# perica3.net
KiCad netlist of a schematic drawn in EAGLE
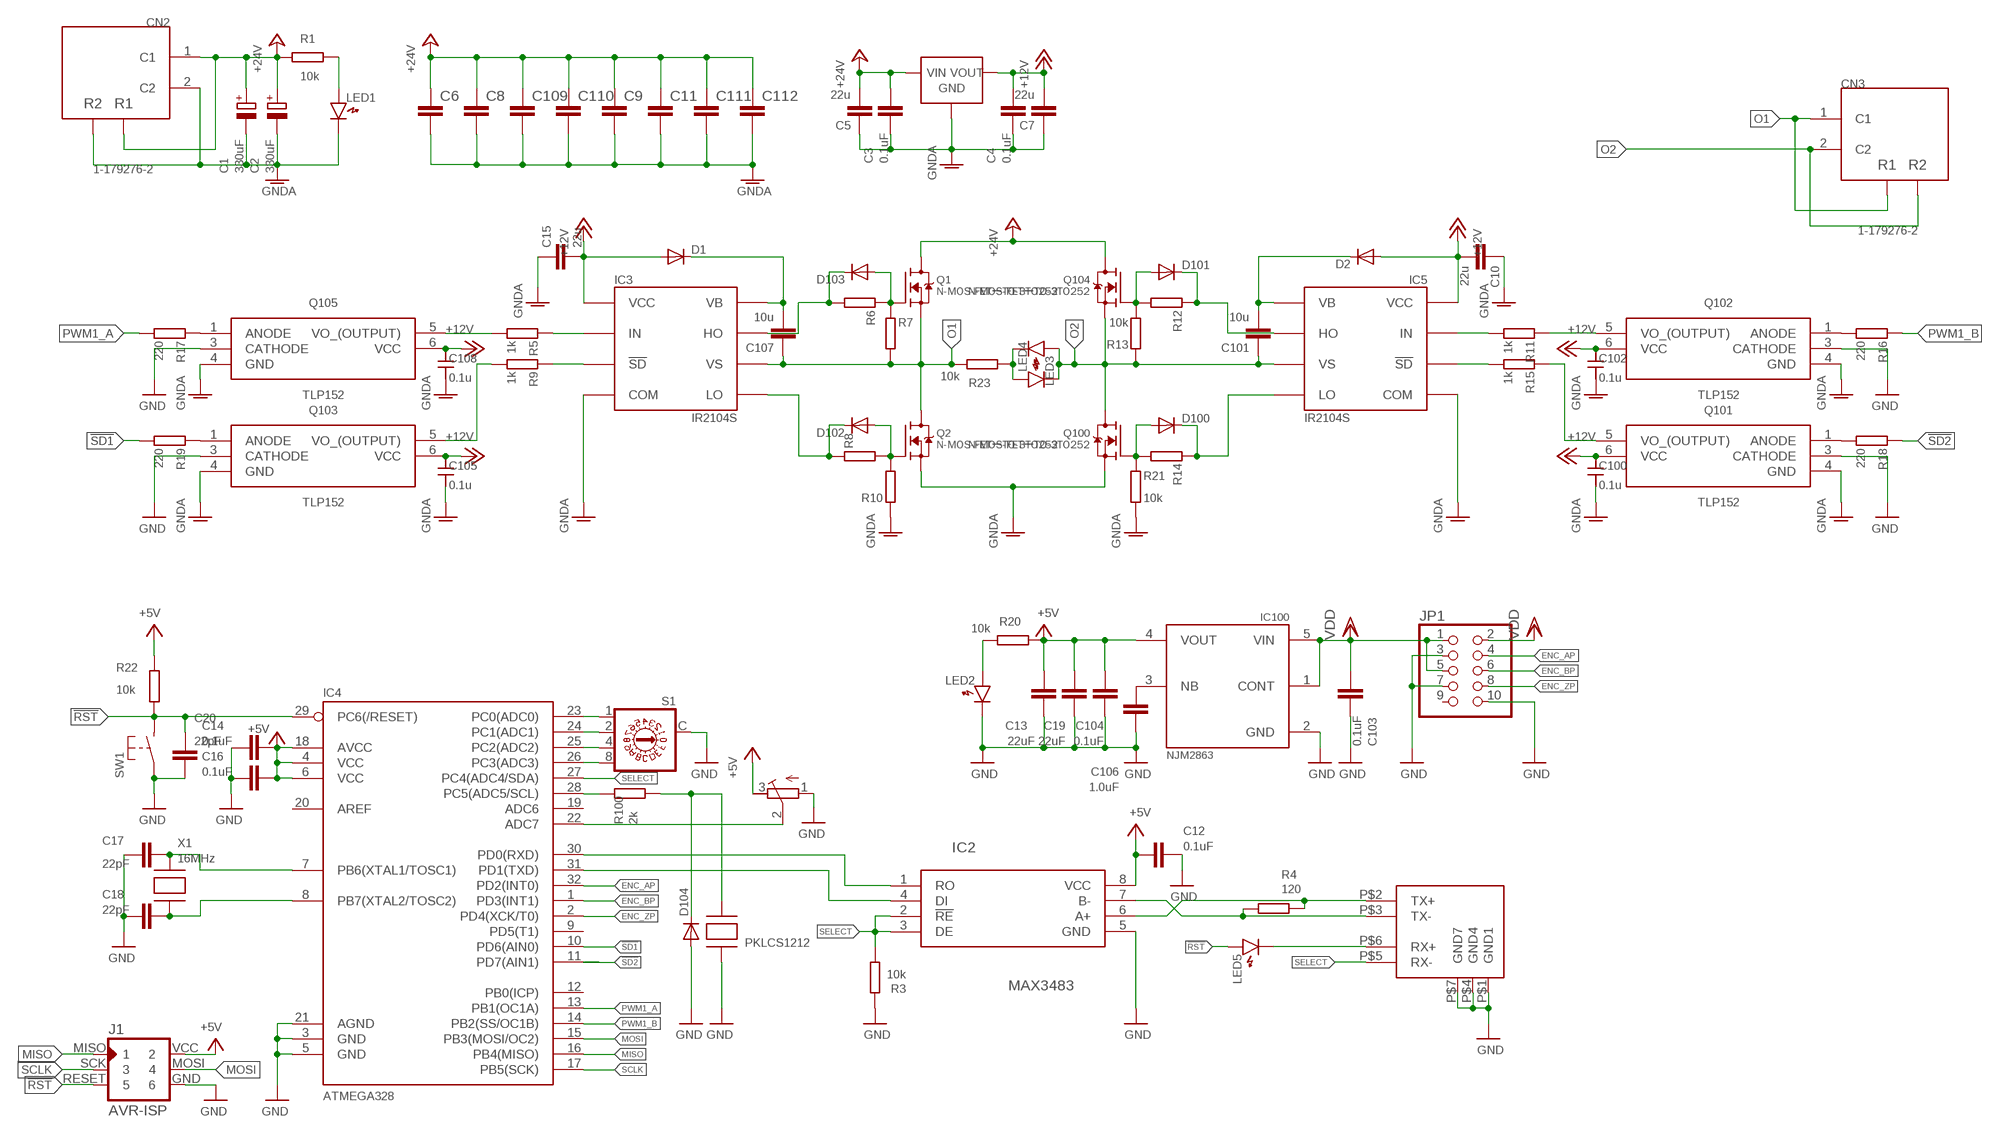
[diagram p0: schematic, sheet 1]

(export (version "E")
  (design (tool "Eeschema 10.0.6"))
  (components
    (comp (ref "C1")
      (value "330uF")
      (footprint "eagle-import:UD-10X10_NICHICON")
      (libsource (lib "eagle-import") (part "CPOL-EUUD-10X10"))
    )
    (comp (ref "C2")
      (value "330uF")
      (footprint "eagle-import:UD-10X10_NICHICON")
      (libsource (lib "eagle-import") (part "CPOL-EUUD-10X10"))
    )
    (comp (ref "C3")
      (value "0.1uF")
      (footprint "eagle-import:C0603K")
      (libsource (lib "eagle-import") (part "resistor_C-EUC0603K"))
    )
    (comp (ref "C4")
      (value "0.1uF")
      (footprint "eagle-import:C0603K")
      (libsource (lib "eagle-import") (part "resistor_C-EUC0603K"))
    )
    (comp (ref "C5")
      (value "22u")
      (footprint "eagle-import:C1206K")
      (libsource (lib "eagle-import") (part "C-EUC1206K"))
    )
    (comp (ref "C6")
      (value "C-EUC1206")
      (footprint "eagle-import:C1206")
      (libsource (lib "eagle-import") (part "C-EUC1206"))
    )
    (comp (ref "C7")
      (value "22u")
      (footprint "eagle-import:C1206K")
      (libsource (lib "eagle-import") (part "C-EUC1206K"))
    )
    (comp (ref "C8")
      (value "C-EUC1206")
      (footprint "eagle-import:C1206")
      (libsource (lib "eagle-import") (part "C-EUC1206"))
    )
    (comp (ref "C9")
      (value "C-EUC1206")
      (footprint "eagle-import:C1206")
      (libsource (lib "eagle-import") (part "C-EUC1206"))
    )
    (comp (ref "C10")
      (value "22u")
      (footprint "eagle-import:C1206K")
      (libsource (lib "eagle-import") (part "C-EUC1206K"))
    )
    (comp (ref "C11")
      (value "C-EUC1206")
      (footprint "eagle-import:C1206")
      (libsource (lib "eagle-import") (part "C-EUC1206"))
    )
    (comp (ref "C12")
      (value "0.1uF")
      (footprint "eagle-import:C0603K")
      (libsource (lib "eagle-import") (part "resistor_C-EUC0603K"))
    )
    (comp (ref "C13")
      (value "22uF")
      (footprint "eagle-import:C0805K")
      (libsource (lib "eagle-import") (part "resistor_C-EUC0805K"))
    )
    (comp (ref "C14")
      (value "0.1uF")
      (footprint "eagle-import:C0603K")
      (libsource (lib "eagle-import") (part "resistor_C-EUC0603K"))
    )
    (comp (ref "C15")
      (value "22u")
      (footprint "eagle-import:C1206K")
      (libsource (lib "eagle-import") (part "C-EUC1206K"))
    )
    (comp (ref "C16")
      (value "0.1uF")
      (footprint "eagle-import:C0603K")
      (libsource (lib "eagle-import") (part "resistor_C-EUC0603K"))
    )
    (comp (ref "C17")
      (value "22pF")
      (footprint "eagle-import:C0603K")
      (libsource (lib "eagle-import") (part "resistor_C-EUC0603K"))
    )
    (comp (ref "C18")
      (value "22pF")
      (footprint "eagle-import:C0603K")
      (libsource (lib "eagle-import") (part "resistor_C-EUC0603K"))
    )
    (comp (ref "C19")
      (value "22uF")
      (footprint "eagle-import:C0805K")
      (libsource (lib "eagle-import") (part "resistor_C-EUC0805K"))
    )
    (comp (ref "C20")
      (value "22pF")
      (footprint "eagle-import:C0603K")
      (libsource (lib "eagle-import") (part "resistor_C-EUC0603K"))
    )
    (comp (ref "C100")
      (value "0.1u")
      (footprint "eagle-import:SMD1608")
      (libsource (lib "eagle-import") (part "CAPACTOR1608"))
    )
    (comp (ref "C101")
      (value "10u")
      (footprint "eagle-import:C1206K")
      (libsource (lib "eagle-import") (part "C-EUC1206K"))
    )
    (comp (ref "C102")
      (value "0.1u")
      (footprint "eagle-import:SMD1608")
      (libsource (lib "eagle-import") (part "CAPACTOR1608"))
    )
    (comp (ref "C103")
      (value "0.1uF")
      (footprint "eagle-import:C0603K")
      (libsource (lib "eagle-import") (part "resistor_C-EUC0603K"))
    )
    (comp (ref "C104")
      (value "0.1uF")
      (footprint "eagle-import:C0603K")
      (libsource (lib "eagle-import") (part "resistor_C-EUC0603K"))
    )
    (comp (ref "C105")
      (value "0.1u")
      (footprint "eagle-import:SMD1608")
      (libsource (lib "eagle-import") (part "CAPACTOR1608"))
    )
    (comp (ref "C106")
      (value "1.0uF")
      (footprint "eagle-import:C0603K")
      (libsource (lib "eagle-import") (part "resistor_C-EUC0603K"))
    )
    (comp (ref "C107")
      (value "10u")
      (footprint "eagle-import:C1206K")
      (libsource (lib "eagle-import") (part "C-EUC1206K"))
    )
    (comp (ref "C108")
      (value "0.1u")
      (footprint "eagle-import:SMD1608")
      (libsource (lib "eagle-import") (part "CAPACTOR1608"))
    )
    (comp (ref "C109")
      (value "C-EUC1206")
      (footprint "eagle-import:C1206")
      (libsource (lib "eagle-import") (part "C-EUC1206"))
    )
    (comp (ref "C110")
      (value "C-EUC1206")
      (footprint "eagle-import:C1206")
      (libsource (lib "eagle-import") (part "C-EUC1206"))
    )
    (comp (ref "C111")
      (value "C-EUC1206")
      (footprint "eagle-import:C1206")
      (libsource (lib "eagle-import") (part "C-EUC1206"))
    )
    (comp (ref "C112")
      (value "C-EUC1206")
      (footprint "eagle-import:C1206")
      (libsource (lib "eagle-import") (part "C-EUC1206"))
    )
    (comp (ref "CN1")
      (value "SATA")
      (footprint "eagle-import:SATA_MOLEX_LLC_0470804001")
      (libsource (lib "eagle-import") (part "SATA"))
    )
    (comp (ref "CN2")
      (value "1-179276-2")
      (footprint "eagle-import:1-179276-2")
      (fields (field (name "MANUFACTURER_PART_NUMBER") "11792762"))
      (libsource (lib "eagle-import") (part "1-179276-2"))
    )
    (comp (ref "CN3")
      (value "1-179276-2")
      (footprint "eagle-import:1-179276-2")
      (fields (field (name "MANUFACTURER_PART_NUMBER") "11792762"))
      (libsource (lib "eagle-import") (part "1-179276-2"))
    )
    (comp (ref "D1")
      (value "DIODE-SOD123")
      (footprint "eagle-import:SOD123")
      (libsource (lib "eagle-import") (part "DIODE-SOD123"))
    )
    (comp (ref "D2")
      (value "DIODE-SOD123")
      (footprint "eagle-import:SOD123")
      (libsource (lib "eagle-import") (part "DIODE-SOD123"))
    )
    (comp (ref "D100")
      (value "DIODE-SOD123")
      (footprint "eagle-import:SOD123")
      (libsource (lib "eagle-import") (part "DIODE-SOD123"))
    )
    (comp (ref "D101")
      (value "DIODE-SOD123")
      (footprint "eagle-import:SOD123")
      (libsource (lib "eagle-import") (part "DIODE-SOD123"))
    )
    (comp (ref "D102")
      (value "DIODE-SOD123")
      (footprint "eagle-import:SOD123")
      (libsource (lib "eagle-import") (part "DIODE-SOD123"))
    )
    (comp (ref "D103")
      (value "DIODE-SOD123")
      (footprint "eagle-import:SOD123")
      (libsource (lib "eagle-import") (part "DIODE-SOD123"))
    )
    (comp (ref "D104")
      (value "DIODE-SOD123")
      (footprint "eagle-import:SOD123")
      (libsource (lib "eagle-import") (part "DIODE-SOD123"))
    )
    (comp (ref "IC1")
      (value "NJM78XX")
      (footprint "eagle-import:TO252")
      (libsource (lib "eagle-import") (part "NJM78XX"))
    )
    (comp (ref "IC2")
      (value "MAX3483")
      (footprint "eagle-import:SO-8")
      (libsource (lib "eagle-import") (part "MAX3488"))
    )
    (comp (ref "IC3")
      (value "IR2104S")
      (footprint "eagle-import:SO-8")
      (libsource (lib "eagle-import") (part "IR2104S"))
    )
    (comp (ref "IC4")
      (value "ATMEGA328")
      (footprint "eagle-import:TQFP32-08")
      (libsource (lib "eagle-import") (part "ATMEGA328"))
    )
    (comp (ref "IC5")
      (value "IR2104S")
      (footprint "eagle-import:SO-8")
      (libsource (lib "eagle-import") (part "IR2104S"))
    )
    (comp (ref "IC100")
      (value "NJM2863")
      (footprint "eagle-import:SOT-23-5")
      (libsource (lib "eagle-import") (part "NJM2863"))
    )
    (comp (ref "J1")
      (value "AVR-ISP")
      (footprint "eagle-import:AVR-ISP-6PIN-SMAILL-SILK")
      (libsource (lib "eagle-import") (part "AVR-ISP-6PINAVR-ISP-6PIN-SMALL-SILK"))
    )
    (comp (ref "JP1")
      (value "PINHD-2X5")
      (footprint "eagle-import:2X05")
      (libsource (lib "eagle-import") (part "PINHD-2X5"))
    )
    (comp (ref "LED1")
      (value "RED")
      (footprint "eagle-import:LED_1608")
      (libsource (lib "eagle-import") (part "LED"))
    )
    (comp (ref "LED2")
      (value "RED")
      (footprint "eagle-import:LED_1608")
      (libsource (lib "eagle-import") (part "LED"))
    )
    (comp (ref "LED3")
      (value "RED")
      (footprint "eagle-import:LED_1608")
      (libsource (lib "eagle-import") (part "LED"))
    )
    (comp (ref "LED4")
      (value "RED")
      (footprint "eagle-import:LED_1608")
      (libsource (lib "eagle-import") (part "LED"))
    )
    (comp (ref "LED5")
      (value "RED")
      (footprint "eagle-import:LED_1608")
      (libsource (lib "eagle-import") (part "LED"))
    )
    (comp (ref "Q1")
      (value "N-MOS-FETーTO-3TO252")
      (footprint "eagle-import:TO252")
      (libsource (lib "eagle-import") (part "N-MOS-FETーTO-3TO252"))
    )
    (comp (ref "Q2")
      (value "N-MOS-FETーTO-3TO252")
      (footprint "eagle-import:TO252")
      (libsource (lib "eagle-import") (part "N-MOS-FETーTO-3TO252"))
    )
    (comp (ref "Q100")
      (value "N-MOS-FETーTO-3TO252")
      (footprint "eagle-import:TO252")
      (libsource (lib "eagle-import") (part "N-MOS-FETーTO-3TO252"))
    )
    (comp (ref "Q101")
      (value "TLP152")
      (footprint "eagle-import:11-4L1S(5-PIN-SOIC)")
      (fields (field (name "MANUFACTURER_PART_NUMBER") "TLP2309") (field (name "RS_PART_NUMBER") "7965241P"))
      (libsource (lib "eagle-import") (part "TLP2309"))
    )
    (comp (ref "Q102")
      (value "TLP152")
      (footprint "eagle-import:11-4L1S(5-PIN-SOIC)")
      (fields (field (name "MANUFACTURER_PART_NUMBER") "TLP2309") (field (name "RS_PART_NUMBER") "7965241P"))
      (libsource (lib "eagle-import") (part "TLP2309"))
    )
    (comp (ref "Q103")
      (value "TLP152")
      (footprint "eagle-import:11-4L1S(5-PIN-SOIC)")
      (fields (field (name "MANUFACTURER_PART_NUMBER") "TLP2309") (field (name "RS_PART_NUMBER") "7965241P"))
      (libsource (lib "eagle-import") (part "TLP2309"))
    )
    (comp (ref "Q104")
      (value "N-MOS-FETーTO-3TO252")
      (footprint "eagle-import:TO252")
      (libsource (lib "eagle-import") (part "N-MOS-FETーTO-3TO252"))
    )
    (comp (ref "Q105")
      (value "TLP152")
      (footprint "eagle-import:11-4L1S(5-PIN-SOIC)")
      (fields (field (name "MANUFACTURER_PART_NUMBER") "TLP2309") (field (name "RS_PART_NUMBER") "7965241P"))
      (libsource (lib "eagle-import") (part "TLP2309"))
    )
    (comp (ref "R1")
      (value "10k")
      (footprint "eagle-import:SMD1608")
      (libsource (lib "eagle-import") (part "REGISTER1068"))
    )
    (comp (ref "R2")
      (value "10k-20k")
      (footprint "eagle-import:RTRIM4G_J")
      (libsource (lib "eagle-import") (part "R-TRIMM4G/J"))
    )
    (comp (ref "R3")
      (value "10k")
      (footprint "eagle-import:SMD1608")
      (libsource (lib "eagle-import") (part "REGISTER1068"))
    )
    (comp (ref "R4")
      (value "120")
      (footprint "eagle-import:SMD1608")
      (libsource (lib "eagle-import") (part "REGISTER1068"))
    )
    (comp (ref "R5")
      (value "1k")
      (footprint "eagle-import:SMD1608")
      (libsource (lib "eagle-import") (part "REGISTER1068"))
    )
    (comp (ref "R6")
      (value "REGISTER1068")
      (footprint "eagle-import:SMD1608")
      (libsource (lib "eagle-import") (part "REGISTER1068"))
    )
    (comp (ref "R7")
      (value "REGISTER1068")
      (footprint "eagle-import:SMD1608")
      (libsource (lib "eagle-import") (part "REGISTER1068"))
    )
    (comp (ref "R8")
      (value "REGISTER1068")
      (footprint "eagle-import:SMD1608")
      (libsource (lib "eagle-import") (part "REGISTER1068"))
    )
    (comp (ref "R9")
      (value "1k")
      (footprint "eagle-import:SMD1608")
      (libsource (lib "eagle-import") (part "REGISTER1068"))
    )
    (comp (ref "R10")
      (value "REGISTER1068")
      (footprint "eagle-import:SMD1608")
      (libsource (lib "eagle-import") (part "REGISTER1068"))
    )
    (comp (ref "R11")
      (value "1k")
      (footprint "eagle-import:SMD1608")
      (libsource (lib "eagle-import") (part "REGISTER1068"))
    )
    (comp (ref "R12")
      (value "REGISTER1068")
      (footprint "eagle-import:SMD1608")
      (libsource (lib "eagle-import") (part "REGISTER1068"))
    )
    (comp (ref "R13")
      (value "10k")
      (footprint "eagle-import:SMD1608")
      (libsource (lib "eagle-import") (part "REGISTER1068"))
    )
    (comp (ref "R14")
      (value "REGISTER1068")
      (footprint "eagle-import:SMD1608")
      (libsource (lib "eagle-import") (part "REGISTER1068"))
    )
    (comp (ref "R15")
      (value "1k")
      (footprint "eagle-import:SMD1608")
      (libsource (lib "eagle-import") (part "REGISTER1068"))
    )
    (comp (ref "R16")
      (value "220")
      (footprint "eagle-import:SMD1608")
      (libsource (lib "eagle-import") (part "REGISTER1068"))
    )
    (comp (ref "R17")
      (value "220")
      (footprint "eagle-import:SMD1608")
      (libsource (lib "eagle-import") (part "REGISTER1068"))
    )
    (comp (ref "R18")
      (value "220")
      (footprint "eagle-import:SMD1608")
      (libsource (lib "eagle-import") (part "REGISTER1068"))
    )
    (comp (ref "R19")
      (value "220")
      (footprint "eagle-import:SMD1608")
      (libsource (lib "eagle-import") (part "REGISTER1068"))
    )
    (comp (ref "R20")
      (value "10k")
      (footprint "eagle-import:SMD1608")
      (libsource (lib "eagle-import") (part "REGISTER1068"))
    )
    (comp (ref "R21")
      (value "10k")
      (footprint "eagle-import:SMD1608")
      (libsource (lib "eagle-import") (part "REGISTER1068"))
    )
    (comp (ref "R22")
      (value "10k")
      (footprint "eagle-import:SMD1608")
      (libsource (lib "eagle-import") (part "REGISTER1068"))
    )
    (comp (ref "R23")
      (value "10k")
      (footprint "eagle-import:SMD1608")
      (libsource (lib "eagle-import") (part "REGISTER1068"))
    )
    (comp (ref "R100")
      (value "2k")
      (footprint "eagle-import:SMD1608")
      (libsource (lib "eagle-import") (part "REGISTER1068"))
    )
    (comp (ref "S1")
      (value "P103")
      (footprint "eagle-import:P103")
      (libsource (lib "eagle-import") (part "P103"))
    )
    (comp (ref "SW1")
      (value "TUCT_SW_MINI")
      (footprint "eagle-import:SW1")
      (libsource (lib "eagle-import") (part "TUCT_SW_MINI"))
    )
    (comp (ref "X1")
      (value "16MHz")
      (footprint "eagle-import:NX5032")
      (libsource (lib "eagle-import") (part "XTALNX5032"))
    )
    (comp (ref "Z1")
      (value "PKLCS1212")
      (footprint "eagle-import:PKLCS1212")
      (libsource (lib "eagle-import") (part "PKLCS1212"))
    )
  )
  (nets
    (net (code "1") (name "+5V") (class "Default")
      (node (ref "C104") (pin "2") (pinfunction "2_2") (pintype "passive"))
      (node (ref "C12") (pin "2") (pinfunction "2_2") (pintype "passive"))
      (node (ref "C13") (pin "1") (pinfunction "1_1") (pintype "passive"))
      (node (ref "C14") (pin "2") (pinfunction "2_2") (pintype "passive"))
      (node (ref "C16") (pin "2") (pinfunction "2_2") (pintype "passive"))
      (node (ref "C19") (pin "1") (pinfunction "1_1") (pintype "passive"))
      (node (ref "IC100") (pin "4") (pinfunction "VOUT_4") (pintype "bidirectional"))
      (node (ref "IC2") (pin "8") (pinfunction "VCC_8") (pintype "power_in"))
      (node (ref "IC4") (pin "18") (pinfunction "AVCC_18") (pintype "bidirectional"))
      (node (ref "IC4") (pin "4") (pinfunction "VCC_4") (pintype "bidirectional"))
      (node (ref "IC4") (pin "6") (pinfunction "VCC_6") (pintype "bidirectional"))
      (node (ref "J1") (pin "VCC") (pinfunction "2_VCC") (pintype "passive"))
      (node (ref "R2") (pin "3") (pinfunction "E_3") (pintype "passive"))
      (node (ref "R20") (pin "2") (pinfunction "2_2") (pintype "passive"))
      (node (ref "R22") (pin "2") (pinfunction "2_2") (pintype "passive"))
    )
    (net (code "2") (name "+12V") (class "Default")
      (node (ref "C10") (pin "2") (pinfunction "2_2") (pintype "passive"))
      (node (ref "C100") (pin "1") (pinfunction "1_1") (pintype "passive"))
      (node (ref "C102") (pin "1") (pinfunction "1_1") (pintype "passive"))
      (node (ref "C105") (pin "1") (pinfunction "1_1") (pintype "passive"))
      (node (ref "C108") (pin "1") (pinfunction "1_1") (pintype "passive"))
      (node (ref "C15") (pin "2") (pinfunction "2_2") (pintype "passive"))
      (node (ref "C4") (pin "2") (pinfunction "2_2") (pintype "passive"))
      (node (ref "C7") (pin "2") (pinfunction "2_2") (pintype "passive"))
      (node (ref "D1") (pin "A") (pinfunction "A_A") (pintype "passive"))
      (node (ref "D2") (pin "A") (pinfunction "A_A") (pintype "passive"))
      (node (ref "IC1") (pin "2") (pinfunction "VOUT_2") (pintype "bidirectional"))
      (node (ref "IC3") (pin "1") (pinfunction "VCC_1") (pintype "bidirectional"))
      (node (ref "IC5") (pin "1") (pinfunction "VCC_1") (pintype "bidirectional"))
      (node (ref "Q101") (pin "6") (pinfunction "VCC_6") (pintype "input"))
      (node (ref "Q102") (pin "6") (pinfunction "VCC_6") (pintype "input"))
      (node (ref "Q103") (pin "6") (pinfunction "VCC_6") (pintype "input"))
      (node (ref "Q105") (pin "6") (pinfunction "VCC_6") (pintype "input"))
    )
    (net (code "3") (name "+24V") (class "Default")
      (node (ref "C1") (pin "+") (pinfunction "+_+") (pintype "passive"))
      (node (ref "C109") (pin "1") (pinfunction "1_1") (pintype "passive"))
      (node (ref "C11") (pin "1") (pinfunction "1_1") (pintype "passive"))
      (node (ref "C110") (pin "1") (pinfunction "1_1") (pintype "passive"))
      (node (ref "C111") (pin "1") (pinfunction "1_1") (pintype "passive"))
      (node (ref "C112") (pin "1") (pinfunction "1_1") (pintype "passive"))
      (node (ref "C2") (pin "+") (pinfunction "+_+") (pintype "passive"))
      (node (ref "C3") (pin "2") (pinfunction "2_2") (pintype "passive"))
      (node (ref "C5") (pin "2") (pinfunction "2_2") (pintype "passive"))
      (node (ref "C6") (pin "1") (pinfunction "1_1") (pintype "passive"))
      (node (ref "C8") (pin "1") (pinfunction "1_1") (pintype "passive"))
      (node (ref "C9") (pin "1") (pinfunction "1_1") (pintype "passive"))
      (node (ref "CN2") (pin "1") (pinfunction "C1_1") (pintype "passive"))
      (node (ref "CN2") (pin "4") (pinfunction "R1_4") (pintype "passive"))
      (node (ref "IC1") (pin "1") (pinfunction "VIN_1") (pintype "bidirectional"))
      (node (ref "Q1") (pin "3") (pinfunction "D_3") (pintype "bidirectional"))
      (node (ref "Q104") (pin "3") (pinfunction "D_3") (pintype "bidirectional"))
      (node (ref "R1") (pin "2") (pinfunction "2_2") (pintype "passive"))
    )
    (net (code "4") (name "/~{RST}") (class "Default")
      (node (ref "C20") (pin "2") (pinfunction "2_2") (pintype "passive"))
      (node (ref "IC4") (pin "29") (pinfunction "PC6(/RESET)_29") (pintype "bidirectional"))
      (node (ref "J1") (pin "RESET") (pinfunction "5_RESET") (pintype "passive"))
      (node (ref "LED5") (pin "A") (pinfunction "A_A") (pintype "passive"))
      (node (ref "R22") (pin "1") (pinfunction "1_1") (pintype "passive"))
      (node (ref "SW1") (pin "P$2") (pinfunction "S_P$2") (pintype "passive"))
    )
    (net (code "5") (name "/~{SD1}") (class "Default")
      (node (ref "IC4") (pin "10") (pinfunction "PD6(AIN0)_10") (pintype "bidirectional"))
      (node (ref "R19") (pin "2") (pinfunction "2_2") (pintype "passive"))
    )
    (net (code "6") (name "/~{SD2}") (class "Default")
      (node (ref "IC4") (pin "11") (pinfunction "PD7(AIN1)_11") (pintype "bidirectional"))
      (node (ref "R18") (pin "1") (pinfunction "1_1") (pintype "passive"))
    )
    (net (code "7") (name "ENC_AP") (class "Default")
      (node (ref "IC4") (pin "32") (pinfunction "PD2(INT0)_32") (pintype "bidirectional"))
      (node (ref "JP1") (pin "4") (pinfunction "4_4") (pintype "passive"))
    )
    (net (code "8") (name "ENC_BP") (class "Default")
      (node (ref "IC4") (pin "1") (pinfunction "PD3(INT1)_1") (pintype "bidirectional"))
      (node (ref "JP1") (pin "6") (pinfunction "6_6") (pintype "passive"))
    )
    (net (code "9") (name "ENC_ZP") (class "Default")
      (node (ref "IC4") (pin "2") (pinfunction "PD4(XCK/T0)_2") (pintype "bidirectional"))
      (node (ref "JP1") (pin "8") (pinfunction "8_8") (pintype "passive"))
    )
    (net (code "10") (name "GND") (class "Default")
      (node (ref "C103") (pin "1") (pinfunction "1_1") (pintype "passive"))
      (node (ref "C104") (pin "1") (pinfunction "1_1") (pintype "passive"))
      (node (ref "C106") (pin "1") (pinfunction "1_1") (pintype "passive"))
      (node (ref "C12") (pin "1") (pinfunction "1_1") (pintype "passive"))
      (node (ref "C13") (pin "2") (pinfunction "2_2") (pintype "passive"))
      (node (ref "C14") (pin "1") (pinfunction "1_1") (pintype "passive"))
      (node (ref "C16") (pin "1") (pinfunction "1_1") (pintype "passive"))
      (node (ref "C17") (pin "1") (pinfunction "1_1") (pintype "passive"))
      (node (ref "C18") (pin "1") (pinfunction "1_1") (pintype "passive"))
      (node (ref "C19") (pin "2") (pinfunction "2_2") (pintype "passive"))
      (node (ref "C20") (pin "1") (pinfunction "1_1") (pintype "passive"))
      (node (ref "CN1") (pin "P$1") (pinfunction "GND1_P$1") (pintype "bidirectional"))
      (node (ref "CN1") (pin "P$4") (pinfunction "GND4_P$4") (pintype "bidirectional"))
      (node (ref "CN1") (pin "P$7") (pinfunction "GND7_P$7") (pintype "bidirectional"))
      (node (ref "D104") (pin "A") (pinfunction "A_A") (pintype "passive"))
      (node (ref "IC100") (pin "2") (pinfunction "GND_2") (pintype "bidirectional"))
      (node (ref "IC2") (pin "5") (pinfunction "GND_5") (pintype "power_in"))
      (node (ref "IC4") (pin "21") (pinfunction "AGND_21") (pintype "bidirectional"))
      (node (ref "IC4") (pin "3") (pinfunction "GND_3") (pintype "bidirectional"))
      (node (ref "IC4") (pin "5") (pinfunction "GND_5") (pintype "bidirectional"))
      (node (ref "J1") (pin "GND") (pinfunction "6_GND") (pintype "passive"))
      (node (ref "JP1") (pin "10") (pinfunction "10_10") (pintype "passive"))
      (node (ref "JP1") (pin "3") (pinfunction "3_3") (pintype "passive"))
      (node (ref "JP1") (pin "7") (pinfunction "7_7") (pintype "passive"))
      (node (ref "LED2") (pin "K") (pinfunction "K_K") (pintype "passive"))
      (node (ref "Q101") (pin "3") (pinfunction "CATHODE_3") (pintype "input"))
      (node (ref "Q102") (pin "3") (pinfunction "CATHODE_3") (pintype "input"))
      (node (ref "Q103") (pin "3") (pinfunction "CATHODE_3") (pintype "input"))
      (node (ref "Q105") (pin "3") (pinfunction "CATHODE_3") (pintype "input"))
      (node (ref "R2") (pin "1") (pinfunction "A_1") (pintype "passive"))
      (node (ref "R3") (pin "2") (pinfunction "2_2") (pintype "passive"))
      (node (ref "S1") (pin "C") (pinfunction "C_C") (pintype "passive"))
      (node (ref "SW1") (pin "P$1") (pinfunction "P_P$1") (pintype "passive"))
      (node (ref "Z1") (pin "P$2") (pinfunction "P$2_P$2") (pintype "bidirectional"))
    )
    (net (code "11") (name "GNDA") (class "Default")
      (node (ref "C1") (pin "-") (pinfunction "-_-") (pintype "passive"))
      (node (ref "C10") (pin "1") (pinfunction "1_1") (pintype "passive"))
      (node (ref "C100") (pin "2") (pinfunction "2_2") (pintype "passive"))
      (node (ref "C102") (pin "2") (pinfunction "2_2") (pintype "passive"))
      (node (ref "C105") (pin "2") (pinfunction "2_2") (pintype "passive"))
      (node (ref "C108") (pin "2") (pinfunction "2_2") (pintype "passive"))
      (node (ref "C109") (pin "2") (pinfunction "2_2") (pintype "passive"))
      (node (ref "C11") (pin "2") (pinfunction "2_2") (pintype "passive"))
      (node (ref "C110") (pin "2") (pinfunction "2_2") (pintype "passive"))
      (node (ref "C111") (pin "2") (pinfunction "2_2") (pintype "passive"))
      (node (ref "C112") (pin "2") (pinfunction "2_2") (pintype "passive"))
      (node (ref "C15") (pin "1") (pinfunction "1_1") (pintype "passive"))
      (node (ref "C2") (pin "-") (pinfunction "-_-") (pintype "passive"))
      (node (ref "C3") (pin "1") (pinfunction "1_1") (pintype "passive"))
      (node (ref "C4") (pin "1") (pinfunction "1_1") (pintype "passive"))
      (node (ref "C5") (pin "1") (pinfunction "1_1") (pintype "passive"))
      (node (ref "C6") (pin "2") (pinfunction "2_2") (pintype "passive"))
      (node (ref "C7") (pin "1") (pinfunction "1_1") (pintype "passive"))
      (node (ref "C8") (pin "2") (pinfunction "2_2") (pintype "passive"))
      (node (ref "C9") (pin "2") (pinfunction "2_2") (pintype "passive"))
      (node (ref "CN2") (pin "2") (pinfunction "C2_2") (pintype "passive"))
      (node (ref "CN2") (pin "3") (pinfunction "R2_3") (pintype "passive"))
      (node (ref "IC1") (pin "3") (pinfunction "GND_3") (pintype "bidirectional"))
      (node (ref "IC3") (pin "4") (pinfunction "COM_4") (pintype "bidirectional"))
      (node (ref "IC5") (pin "4") (pinfunction "COM_4") (pintype "bidirectional"))
      (node (ref "LED1") (pin "K") (pinfunction "K_K") (pintype "passive"))
      (node (ref "Q100") (pin "2") (pinfunction "S_2") (pintype "bidirectional"))
      (node (ref "Q101") (pin "4") (pinfunction "GND_4") (pintype "input"))
      (node (ref "Q102") (pin "4") (pinfunction "GND_4") (pintype "input"))
      (node (ref "Q103") (pin "4") (pinfunction "GND_4") (pintype "input"))
      (node (ref "Q105") (pin "4") (pinfunction "GND_4") (pintype "input"))
      (node (ref "Q2") (pin "2") (pinfunction "S_2") (pintype "bidirectional"))
      (node (ref "R10") (pin "1") (pinfunction "1_1") (pintype "passive"))
      (node (ref "R21") (pin "2") (pinfunction "2_2") (pintype "passive"))
    )
    (net (code "12") (name "MISO") (class "Default")
      (node (ref "IC4") (pin "16") (pinfunction "PB4(MISO)_16") (pintype "bidirectional"))
      (node (ref "J1") (pin "MISO") (pinfunction "1_MISO") (pintype "passive"))
    )
    (net (code "13") (name "MOSI") (class "Default")
      (node (ref "IC4") (pin "15") (pinfunction "PB3(MOSI/OC2)_15") (pintype "bidirectional"))
      (node (ref "J1") (pin "MOSI") (pinfunction "4_MOSI") (pintype "passive"))
    )
    (net (code "14") (name "Net-(CN1-RX+)") (class "Default")
      (node (ref "CN1") (pin "P$6") (pinfunction "RX+_P$6") (pintype "bidirectional"))
      (node (ref "LED5") (pin "K") (pinfunction "K_K") (pintype "passive"))
    )
    (net (code "15") (name "Net-(CN1-TX+)") (class "Default")
      (node (ref "CN1") (pin "P$2") (pinfunction "TX+_P$2") (pintype "bidirectional"))
      (node (ref "IC2") (pin "6") (pinfunction "A+_6") (pintype "bidirectional"))
      (node (ref "R4") (pin "1") (pinfunction "1_1") (pintype "passive"))
    )
    (net (code "16") (name "Net-(CN1-TX-)") (class "Default")
      (node (ref "CN1") (pin "P$3") (pinfunction "TX-_P$3") (pintype "bidirectional"))
      (node (ref "IC2") (pin "7") (pinfunction "B-_7") (pintype "bidirectional"))
      (node (ref "R4") (pin "2") (pinfunction "2_2") (pintype "passive"))
    )
    (net (code "17") (name "Net-(D104-PadC)") (class "Default")
      (node (ref "D104") (pin "C") (pinfunction "C_C") (pintype "passive"))
      (node (ref "R100") (pin "1") (pinfunction "1_1") (pintype "passive"))
      (node (ref "Z1") (pin "P$1") (pinfunction "P$1_P$1") (pintype "bidirectional"))
    )
    (net (code "18") (name "Net-(IC2-DI)") (class "Default")
      (node (ref "IC2") (pin "4") (pinfunction "DI_4") (pintype "input"))
      (node (ref "IC4") (pin "31") (pinfunction "PD1(TXD)_31") (pintype "bidirectional"))
    )
    (net (code "19") (name "Net-(IC2-RO)") (class "Default")
      (node (ref "IC2") (pin "1") (pinfunction "RO_1") (pintype "output"))
      (node (ref "IC4") (pin "30") (pinfunction "PD0(RXD)_30") (pintype "bidirectional"))
    )
    (net (code "20") (name "Net-(IC3-HO)") (class "Default")
      (node (ref "D103") (pin "C") (pinfunction "C_C") (pintype "passive"))
      (node (ref "IC3") (pin "7") (pinfunction "HO_7") (pintype "bidirectional"))
      (node (ref "R6") (pin "2") (pinfunction "2_2") (pintype "passive"))
    )
    (net (code "21") (name "Net-(IC3-IN)") (class "Default")
      (node (ref "IC3") (pin "2") (pinfunction "IN_2") (pintype "bidirectional"))
      (node (ref "R5") (pin "1") (pinfunction "1_1") (pintype "passive"))
    )
    (net (code "22") (name "Net-(IC3-LO)") (class "Default")
      (node (ref "D102") (pin "C") (pinfunction "C_C") (pintype "passive"))
      (node (ref "IC3") (pin "5") (pinfunction "LO_5") (pintype "bidirectional"))
      (node (ref "R8") (pin "1") (pinfunction "1_1") (pintype "passive"))
    )
    (net (code "23") (name "Net-(IC3-VB)") (class "Default")
      (node (ref "C107") (pin "2") (pinfunction "2_2") (pintype "passive"))
      (node (ref "D1") (pin "C") (pinfunction "C_C") (pintype "passive"))
      (node (ref "IC3") (pin "8") (pinfunction "VB_8") (pintype "bidirectional"))
    )
    (net (code "24") (name "Net-(IC3-~{SD})") (class "Default")
      (node (ref "IC3") (pin "3") (pinfunction "~{SD}_3") (pintype "bidirectional"))
      (node (ref "R9") (pin "1") (pinfunction "1_1") (pintype "passive"))
    )
    (net (code "25") (name "Net-(IC4-ADC7)") (class "Default")
      (node (ref "IC4") (pin "22") (pinfunction "ADC7_22") (pintype "bidirectional"))
      (node (ref "R2") (pin "2") (pinfunction "S_2") (pintype "passive"))
    )
    (net (code "26") (name "Net-(IC4-PB6(XTAL1{slash}TOSC1))") (class "Default")
      (node (ref "C17") (pin "2") (pinfunction "2_2") (pintype "passive"))
      (node (ref "IC4") (pin "7") (pinfunction "PB6(XTAL1/TOSC1)_7") (pintype "bidirectional"))
      (node (ref "X1") (pin "P$2") (pinfunction "P$2_P$2") (pintype "bidirectional"))
    )
    (net (code "27") (name "Net-(IC4-PB7(XTAL2{slash}TOSC2))") (class "Default")
      (node (ref "C18") (pin "2") (pinfunction "2_2") (pintype "passive"))
      (node (ref "IC4") (pin "8") (pinfunction "PB7(XTAL2/TOSC2)_8") (pintype "bidirectional"))
      (node (ref "X1") (pin "P$1") (pinfunction "P$1_P$1") (pintype "bidirectional"))
    )
    (net (code "28") (name "Net-(IC4-PC0(ADC0))") (class "Default")
      (node (ref "IC4") (pin "23") (pinfunction "PC0(ADC0)_23") (pintype "bidirectional"))
      (node (ref "S1") (pin "1") (pinfunction "1_1") (pintype "passive"))
    )
    (net (code "29") (name "Net-(IC4-PC1(ADC1))") (class "Default")
      (node (ref "IC4") (pin "24") (pinfunction "PC1(ADC1)_24") (pintype "bidirectional"))
      (node (ref "S1") (pin "2") (pinfunction "2_2") (pintype "passive"))
    )
    (net (code "30") (name "Net-(IC4-PC2(ADC2))") (class "Default")
      (node (ref "IC4") (pin "25") (pinfunction "PC2(ADC2)_25") (pintype "bidirectional"))
      (node (ref "S1") (pin "4") (pinfunction "4_4") (pintype "passive"))
    )
    (net (code "31") (name "Net-(IC4-PC3(ADC3))") (class "Default")
      (node (ref "IC4") (pin "26") (pinfunction "PC3(ADC3)_26") (pintype "bidirectional"))
      (node (ref "S1") (pin "8") (pinfunction "8_8") (pintype "passive"))
    )
    (net (code "32") (name "Net-(IC4-PC5(ADC5{slash}SCL))") (class "Default")
      (node (ref "IC4") (pin "28") (pinfunction "PC5(ADC5/SCL)_28") (pintype "bidirectional"))
      (node (ref "R100") (pin "2") (pinfunction "2_2") (pintype "passive"))
    )
    (net (code "33") (name "Net-(IC5-HO)") (class "Default")
      (node (ref "D101") (pin "C") (pinfunction "C_C") (pintype "passive"))
      (node (ref "IC5") (pin "7") (pinfunction "HO_7") (pintype "bidirectional"))
      (node (ref "R12") (pin "1") (pinfunction "1_1") (pintype "passive"))
    )
    (net (code "34") (name "Net-(IC5-IN)") (class "Default")
      (node (ref "IC5") (pin "2") (pinfunction "IN_2") (pintype "bidirectional"))
      (node (ref "R11") (pin "2") (pinfunction "2_2") (pintype "passive"))
    )
    (net (code "35") (name "Net-(IC5-LO)") (class "Default")
      (node (ref "D100") (pin "C") (pinfunction "C_C") (pintype "passive"))
      (node (ref "IC5") (pin "5") (pinfunction "LO_5") (pintype "bidirectional"))
      (node (ref "R14") (pin "1") (pinfunction "1_1") (pintype "passive"))
    )
    (net (code "36") (name "Net-(IC5-VB)") (class "Default")
      (node (ref "C101") (pin "2") (pinfunction "2_2") (pintype "passive"))
      (node (ref "D2") (pin "C") (pinfunction "C_C") (pintype "passive"))
      (node (ref "IC5") (pin "8") (pinfunction "VB_8") (pintype "bidirectional"))
    )
    (net (code "37") (name "Net-(IC5-~{SD})") (class "Default")
      (node (ref "IC5") (pin "3") (pinfunction "~{SD}_3") (pintype "bidirectional"))
      (node (ref "R15") (pin "2") (pinfunction "2_2") (pintype "passive"))
    )
    (net (code "38") (name "Net-(IC100-NB)") (class "Default")
      (node (ref "C106") (pin "2") (pinfunction "2_2") (pintype "passive"))
      (node (ref "IC100") (pin "3") (pinfunction "NB_3") (pintype "bidirectional"))
    )
    (net (code "39") (name "Net-(LED1-PadA)") (class "Default")
      (node (ref "LED1") (pin "A") (pinfunction "A_A") (pintype "passive"))
      (node (ref "R1") (pin "1") (pinfunction "1_1") (pintype "passive"))
    )
    (net (code "40") (name "Net-(LED2-PadA)") (class "Default")
      (node (ref "LED2") (pin "A") (pinfunction "A_A") (pintype "passive"))
      (node (ref "R20") (pin "1") (pinfunction "1_1") (pintype "passive"))
    )
    (net (code "41") (name "Net-(LED3-PadK)") (class "Default")
      (node (ref "LED3") (pin "K") (pinfunction "K_K") (pintype "passive"))
      (node (ref "LED4") (pin "A") (pinfunction "A_A") (pintype "passive"))
      (node (ref "R23") (pin "2") (pinfunction "2_2") (pintype "passive"))
    )
    (net (code "42") (name "Net-(Q1-G)") (class "Default")
      (node (ref "D103") (pin "A") (pinfunction "A_A") (pintype "passive"))
      (node (ref "Q1") (pin "1") (pinfunction "G_1") (pintype "bidirectional"))
      (node (ref "R6") (pin "1") (pinfunction "1_1") (pintype "passive"))
      (node (ref "R7") (pin "1") (pinfunction "1_1") (pintype "passive"))
    )
    (net (code "43") (name "Net-(Q2-G)") (class "Default")
      (node (ref "D102") (pin "A") (pinfunction "A_A") (pintype "passive"))
      (node (ref "Q2") (pin "1") (pinfunction "G_1") (pintype "bidirectional"))
      (node (ref "R10") (pin "2") (pinfunction "2_2") (pintype "passive"))
      (node (ref "R8") (pin "2") (pinfunction "2_2") (pintype "passive"))
    )
    (net (code "44") (name "Net-(Q100-G)") (class "Default")
      (node (ref "D100") (pin "A") (pinfunction "A_A") (pintype "passive"))
      (node (ref "Q100") (pin "1") (pinfunction "G_1") (pintype "bidirectional"))
      (node (ref "R14") (pin "2") (pinfunction "2_2") (pintype "passive"))
      (node (ref "R21") (pin "1") (pinfunction "1_1") (pintype "passive"))
    )
    (net (code "45") (name "Net-(Q101-ANODE)") (class "Default")
      (node (ref "Q101") (pin "1") (pinfunction "ANODE_1") (pintype "input"))
      (node (ref "R18") (pin "2") (pinfunction "2_2") (pintype "passive"))
    )
    (net (code "46") (name "Net-(Q101-VO_(OUTPUT))") (class "Default")
      (node (ref "Q101") (pin "5") (pinfunction "VO_(OUTPUT)_5") (pintype "input"))
      (node (ref "R15") (pin "1") (pinfunction "1_1") (pintype "passive"))
    )
    (net (code "47") (name "Net-(Q102-ANODE)") (class "Default")
      (node (ref "Q102") (pin "1") (pinfunction "ANODE_1") (pintype "input"))
      (node (ref "R16") (pin "2") (pinfunction "2_2") (pintype "passive"))
    )
    (net (code "48") (name "Net-(Q102-VO_(OUTPUT))") (class "Default")
      (node (ref "Q102") (pin "5") (pinfunction "VO_(OUTPUT)_5") (pintype "input"))
      (node (ref "R11") (pin "1") (pinfunction "1_1") (pintype "passive"))
    )
    (net (code "49") (name "Net-(Q103-ANODE)") (class "Default")
      (node (ref "Q103") (pin "1") (pinfunction "ANODE_1") (pintype "input"))
      (node (ref "R19") (pin "1") (pinfunction "1_1") (pintype "passive"))
    )
    (net (code "50") (name "Net-(Q103-VO_(OUTPUT))") (class "Default")
      (node (ref "Q103") (pin "5") (pinfunction "VO_(OUTPUT)_5") (pintype "input"))
      (node (ref "R9") (pin "2") (pinfunction "2_2") (pintype "passive"))
    )
    (net (code "51") (name "Net-(Q104-G)") (class "Default")
      (node (ref "D101") (pin "A") (pinfunction "A_A") (pintype "passive"))
      (node (ref "Q104") (pin "1") (pinfunction "G_1") (pintype "bidirectional"))
      (node (ref "R12") (pin "2") (pinfunction "2_2") (pintype "passive"))
      (node (ref "R13") (pin "2") (pinfunction "2_2") (pintype "passive"))
    )
    (net (code "52") (name "Net-(Q105-ANODE)") (class "Default")
      (node (ref "Q105") (pin "1") (pinfunction "ANODE_1") (pintype "input"))
      (node (ref "R17") (pin "1") (pinfunction "1_1") (pintype "passive"))
    )
    (net (code "53") (name "Net-(Q105-VO_(OUTPUT))") (class "Default")
      (node (ref "Q105") (pin "5") (pinfunction "VO_(OUTPUT)_5") (pintype "input"))
      (node (ref "R5") (pin "2") (pinfunction "2_2") (pintype "passive"))
    )
    (net (code "54") (name "O1") (class "Default")
      (node (ref "C107") (pin "1") (pinfunction "1_1") (pintype "passive"))
      (node (ref "CN3") (pin "1") (pinfunction "C1_1") (pintype "passive"))
      (node (ref "CN3") (pin "4") (pinfunction "R1_4") (pintype "passive"))
      (node (ref "IC3") (pin "6") (pinfunction "VS_6") (pintype "bidirectional"))
      (node (ref "Q1") (pin "2") (pinfunction "S_2") (pintype "bidirectional"))
      (node (ref "Q2") (pin "3") (pinfunction "D_3") (pintype "bidirectional"))
      (node (ref "R23") (pin "1") (pinfunction "1_1") (pintype "passive"))
      (node (ref "R7") (pin "2") (pinfunction "2_2") (pintype "passive"))
    )
    (net (code "55") (name "O2") (class "Default")
      (node (ref "C101") (pin "1") (pinfunction "1_1") (pintype "passive"))
      (node (ref "CN3") (pin "2") (pinfunction "C2_2") (pintype "passive"))
      (node (ref "CN3") (pin "3") (pinfunction "R2_3") (pintype "passive"))
      (node (ref "IC5") (pin "6") (pinfunction "VS_6") (pintype "bidirectional"))
      (node (ref "LED3") (pin "A") (pinfunction "A_A") (pintype "passive"))
      (node (ref "LED4") (pin "K") (pinfunction "K_K") (pintype "passive"))
      (node (ref "Q100") (pin "3") (pinfunction "D_3") (pintype "bidirectional"))
      (node (ref "Q104") (pin "2") (pinfunction "S_2") (pintype "bidirectional"))
      (node (ref "R13") (pin "1") (pinfunction "1_1") (pintype "passive"))
    )
    (net (code "56") (name "PWM1_A") (class "Default")
      (node (ref "IC4") (pin "13") (pinfunction "PB1(OC1A)_13") (pintype "bidirectional"))
      (node (ref "R17") (pin "2") (pinfunction "2_2") (pintype "passive"))
    )
    (net (code "57") (name "PWM1_B") (class "Default")
      (node (ref "IC4") (pin "14") (pinfunction "PB2(SS/OC1B)_14") (pintype "bidirectional"))
      (node (ref "R16") (pin "1") (pinfunction "1_1") (pintype "passive"))
    )
    (net (code "58") (name "SCLK") (class "Default")
      (node (ref "IC4") (pin "17") (pinfunction "PB5(SCK)_17") (pintype "bidirectional"))
      (node (ref "J1") (pin "SCK") (pinfunction "3_SCK") (pintype "passive"))
    )
    (net (code "59") (name "SELECT") (class "Default")
      (node (ref "CN1") (pin "P$5") (pinfunction "RX-_P$5") (pintype "bidirectional"))
      (node (ref "IC2") (pin "2") (pinfunction "~{RE}_2") (pintype "input"))
      (node (ref "IC2") (pin "3") (pinfunction "DE_3") (pintype "input"))
      (node (ref "IC4") (pin "27") (pinfunction "PC4(ADC4/SDA)_27") (pintype "bidirectional"))
      (node (ref "R3") (pin "1") (pinfunction "1_1") (pintype "passive"))
    )
    (net (code "60") (name "VDD") (class "Default")
      (node (ref "C103") (pin "2") (pinfunction "2_2") (pintype "passive"))
      (node (ref "IC100") (pin "1") (pinfunction "CONT_1") (pintype "bidirectional"))
      (node (ref "IC100") (pin "5") (pinfunction "VIN_5") (pintype "bidirectional"))
      (node (ref "JP1") (pin "1") (pinfunction "1_1") (pintype "passive"))
      (node (ref "JP1") (pin "2") (pinfunction "2_2") (pintype "passive"))
      (node (ref "JP1") (pin "5") (pinfunction "5_5") (pintype "passive"))
    )
    (net (code "61") (name "unconnected-(IC4-ADC6-Pad19)") (class "Default")
      (node (ref "IC4") (pin "19") (pinfunction "ADC6_19") (pintype "bidirectional"))
    )
    (net (code "62") (name "unconnected-(IC4-AREF-Pad20)") (class "Default")
      (node (ref "IC4") (pin "20") (pinfunction "AREF_20") (pintype "bidirectional"))
    )
    (net (code "63") (name "unconnected-(IC4-PB0(ICP)-Pad12)") (class "Default")
      (node (ref "IC4") (pin "12") (pinfunction "PB0(ICP)_12") (pintype "bidirectional"))
    )
    (net (code "64") (name "unconnected-(IC4-PD5(T1)-Pad9)") (class "Default")
      (node (ref "IC4") (pin "9") (pinfunction "PD5(T1)_9") (pintype "bidirectional"))
    )
    (net (code "65") (name "unconnected-(JP1-Pad9)") (class "Default")
      (node (ref "JP1") (pin "9") (pinfunction "9_9") (pintype "passive"))
    )
  )
)
